# Sensor_Board_0x02_Temperature_Humidity_S.net
KiCad netlist of a schematic drawn in EAGLE
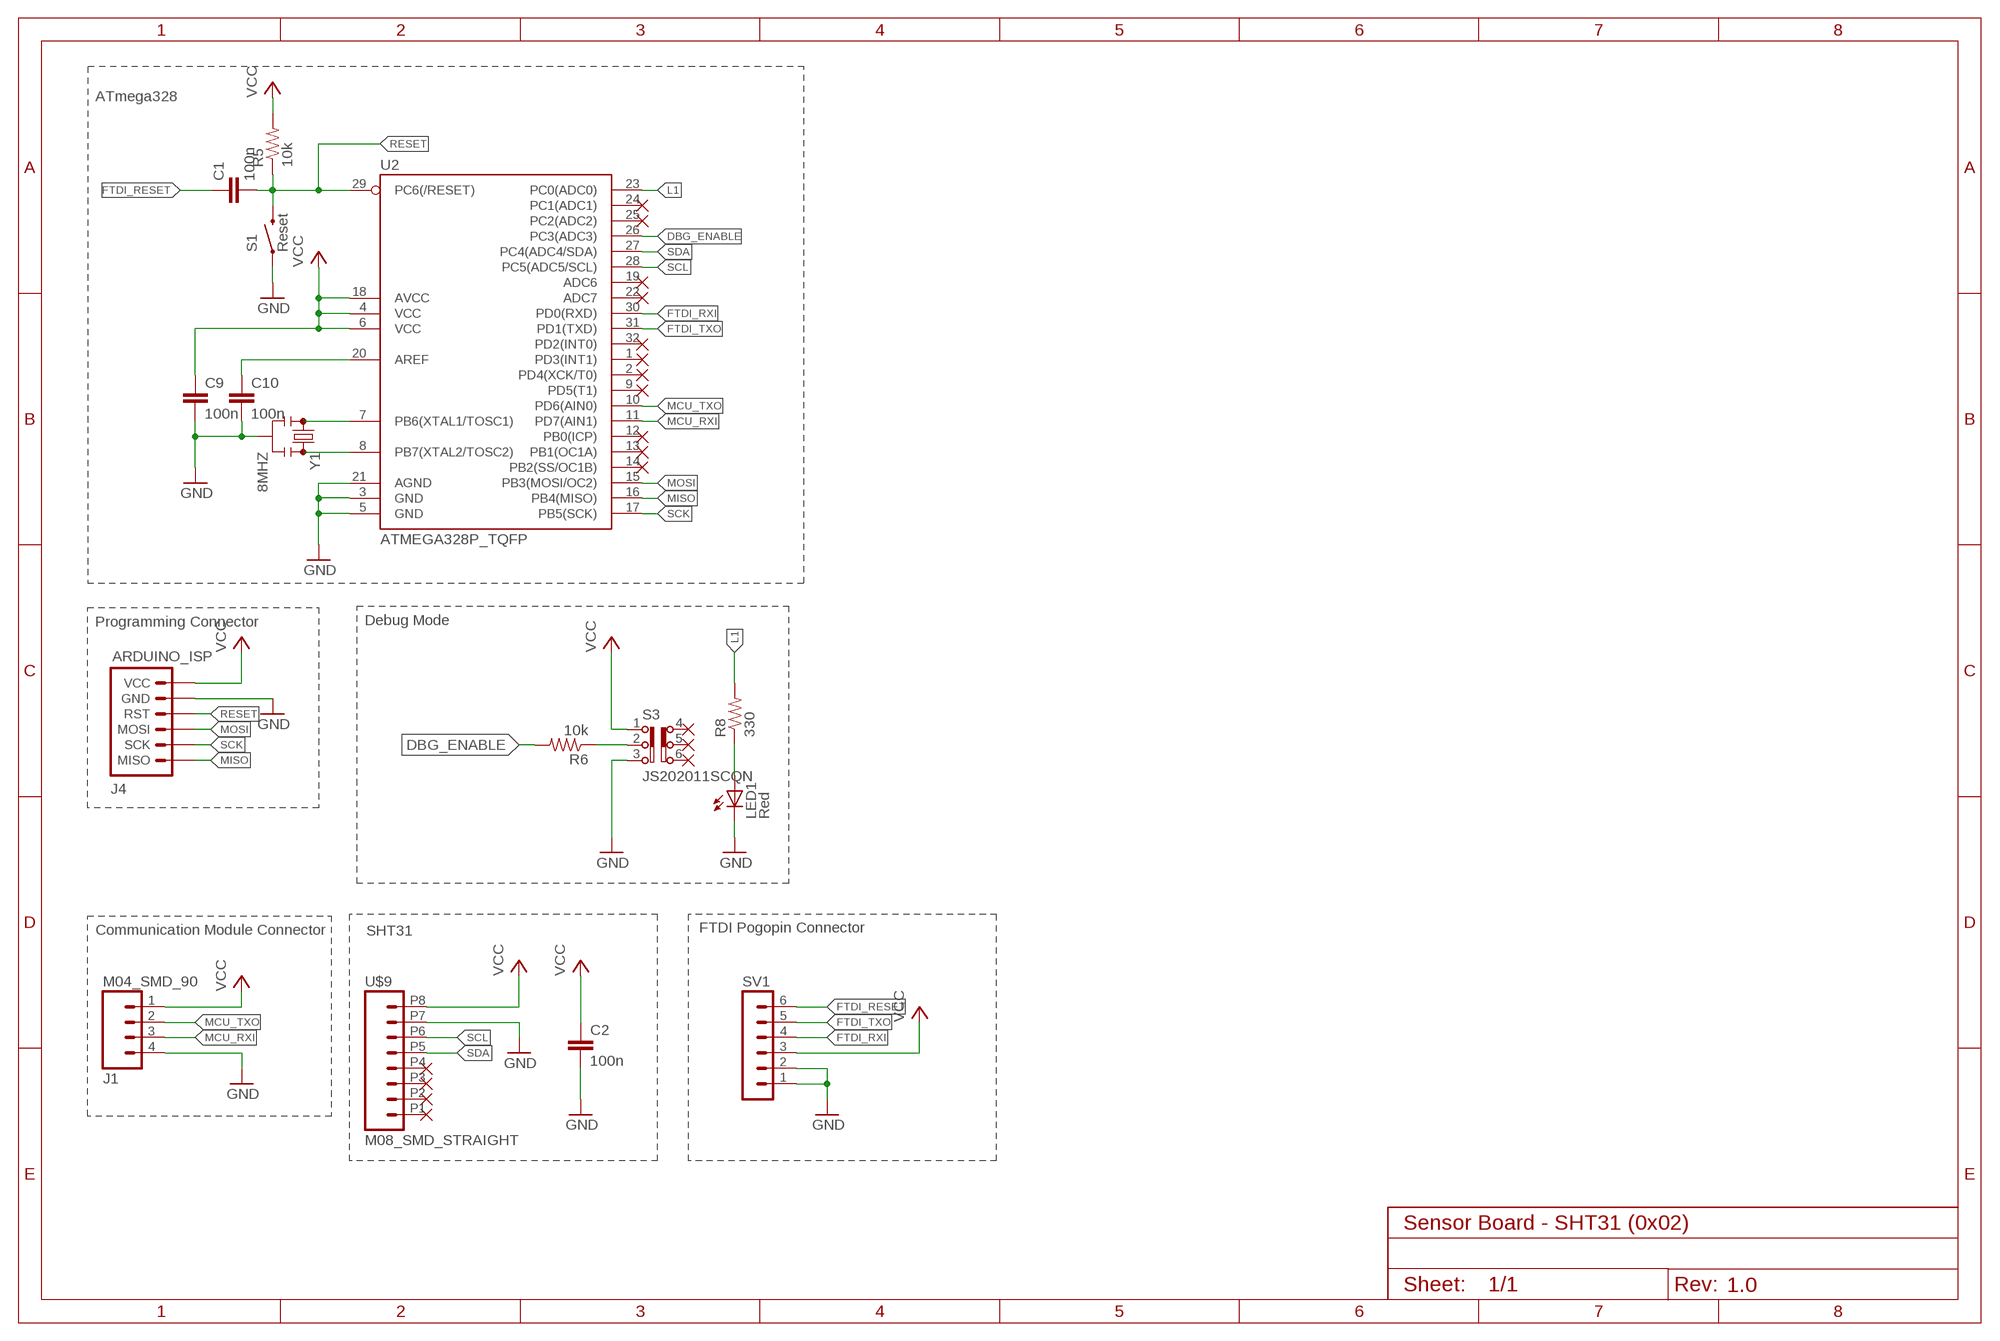
[diagram p0: schematic, sheet 1]

(export (version "E")
  (design (tool "Eeschema 10.0.6"))
  (components
    (comp (ref "C1")
      (value "100n")
      (footprint "eagle-import:C0805")
      (libsource (lib "eagle-import") (part "C"))
    )
    (comp (ref "C2")
      (value "100n")
      (footprint "eagle-import:C0805")
      (libsource (lib "eagle-import") (part "C"))
    )
    (comp (ref "C9")
      (value "100n")
      (footprint "eagle-import:C0805")
      (libsource (lib "eagle-import") (part "C"))
    )
    (comp (ref "C10")
      (value "100n")
      (footprint "eagle-import:C0805")
      (libsource (lib "eagle-import") (part "C"))
    )
    (comp (ref "J1")
      (value "M04_SMD_90")
      (footprint "eagle-import:M04_SMD_90")
      (libsource (lib "eagle-import") (part "M04_SMD_90"))
    )
    (comp (ref "J4")
      (value "ARDUINO_ISP")
      (footprint "eagle-import:M-2X3")
      (libsource (lib "eagle-import") (part "ARDUINO_ISP"))
    )
    (comp (ref "LED1")
      (value "Red")
      (footprint "eagle-import:SML0805")
      (libsource (lib "eagle-import") (part "LEDSML0805"))
    )
    (comp (ref "R5")
      (value "10k")
      (footprint "eagle-import:0805")
      (libsource (lib "eagle-import") (part "RESISTOR0805-RES"))
    )
    (comp (ref "R6")
      (value "10k")
      (footprint "eagle-import:0805")
      (libsource (lib "eagle-import") (part "RESISTOR0805-RES"))
    )
    (comp (ref "R8")
      (value "330")
      (footprint "eagle-import:0805")
      (libsource (lib "eagle-import") (part "RESISTOR0805-RES"))
    )
    (comp (ref "S1")
      (value "Reset")
      (footprint "eagle-import:M-PUSHBUTTON-SMD")
      (libsource (lib "eagle-import") (part "PUSHBUTTON"))
    )
    (comp (ref "S3")
      (value "JS202011SCQN")
      (footprint "eagle-import:JS202011SCQN")
      (libsource (lib "eagle-import") (part "JS202011SCQN"))
    )
    (comp (ref "SV1")
      (value "MA06-1")
      (footprint "eagle-import:MA06-1")
      (libsource (lib "eagle-import") (part "MA06-1"))
    )
    (comp (ref "U$9")
      (value "M08_SMD_STRAIGHT")
      (footprint "eagle-import:M08_SMD_STRAIGHT")
      (libsource (lib "eagle-import") (part "M08_SMD_STRAIGHT"))
    )
    (comp (ref "U2")
      (value "ATMEGA328P_TQFP")
      (footprint "eagle-import:TQFP32-08")
      (libsource (lib "eagle-import") (part "ATMEGA328P_TQFP"))
    )
    (comp (ref "Y1")
      (value "8MHZ")
      (footprint "eagle-import:RESONATOR-SMD")
      (libsource (lib "eagle-import") (part "RESONATOR8MHZ"))
    )
  )
  (nets
    (net (code "1") (name "DBG_ENABLE") (class "Default")
      (node (ref "R6") (pin "2") (pinfunction "2_2") (pintype "passive"))
      (node (ref "U2") (pin "26") (pinfunction "PC3(ADC3)_26") (pintype "bidirectional"))
    )
    (net (code "2") (name "FTDI_RESET") (class "Default")
      (node (ref "C1") (pin "1") (pinfunction "1_1") (pintype "passive"))
      (node (ref "SV1") (pin "6") (pinfunction "6_6") (pintype "passive"))
    )
    (net (code "3") (name "FTDI_RXI") (class "Default")
      (node (ref "SV1") (pin "4") (pinfunction "4_4") (pintype "passive"))
      (node (ref "U2") (pin "30") (pinfunction "PD0(RXD)_30") (pintype "bidirectional"))
    )
    (net (code "4") (name "FTDI_TXO") (class "Default")
      (node (ref "SV1") (pin "5") (pinfunction "5_5") (pintype "passive"))
      (node (ref "U2") (pin "31") (pinfunction "PD1(TXD)_31") (pintype "bidirectional"))
    )
    (net (code "5") (name "GND") (class "Default")
      (node (ref "C10") (pin "2") (pinfunction "2_2") (pintype "passive"))
      (node (ref "C2") (pin "2") (pinfunction "2_2") (pintype "passive"))
      (node (ref "C9") (pin "2") (pinfunction "2_2") (pintype "passive"))
      (node (ref "J1") (pin "4") (pinfunction "4_4") (pintype "passive"))
      (node (ref "J4") (pin "P$5") (pinfunction "GND_P$5") (pintype "passive"))
      (node (ref "LED1") (pin "C") (pinfunction "C_C") (pintype "passive"))
      (node (ref "S1") (pin "1") (pinfunction "LEFT_1") (pintype "passive"))
      (node (ref "S1") (pin "2") (pinfunction "LEFT_2") (pintype "passive"))
      (node (ref "S3") (pin "3") (pinfunction "3_3") (pintype "passive"))
      (node (ref "SV1") (pin "1") (pinfunction "1_1") (pintype "passive"))
      (node (ref "SV1") (pin "2") (pinfunction "2_2") (pintype "passive"))
      (node (ref "U$9") (pin "P7") (pinfunction "7_P7") (pintype "passive"))
      (node (ref "U2") (pin "21") (pinfunction "AGND_21") (pintype "bidirectional"))
      (node (ref "U2") (pin "3") (pinfunction "GND_3") (pintype "bidirectional"))
      (node (ref "U2") (pin "5") (pinfunction "GND_5") (pintype "bidirectional"))
      (node (ref "Y1") (pin "2") (pinfunction "2_2") (pintype "passive"))
    )
    (net (code "6") (name "L1") (class "Default")
      (node (ref "R8") (pin "2") (pinfunction "2_2") (pintype "passive"))
      (node (ref "U2") (pin "23") (pinfunction "PC0(ADC0)_23") (pintype "bidirectional"))
    )
    (net (code "7") (name "MCU_RXI") (class "Default")
      (node (ref "J1") (pin "3") (pinfunction "3_3") (pintype "passive"))
      (node (ref "U2") (pin "11") (pinfunction "PD7(AIN1)_11") (pintype "bidirectional"))
    )
    (net (code "8") (name "MCU_TXO") (class "Default")
      (node (ref "J1") (pin "2") (pinfunction "2_2") (pintype "passive"))
      (node (ref "U2") (pin "10") (pinfunction "PD6(AIN0)_10") (pintype "bidirectional"))
    )
    (net (code "9") (name "MISO") (class "Default")
      (node (ref "J4") (pin "P$1") (pinfunction "MISO_P$1") (pintype "passive"))
      (node (ref "U2") (pin "16") (pinfunction "PB4(MISO)_16") (pintype "bidirectional"))
    )
    (net (code "10") (name "MOSI") (class "Default")
      (node (ref "J4") (pin "P$3") (pinfunction "MOSI_P$3") (pintype "passive"))
      (node (ref "U2") (pin "15") (pinfunction "PB3(MOSI/OC2)_15") (pintype "bidirectional"))
    )
    (net (code "11") (name "Net-(LED1-PadA)") (class "Default")
      (node (ref "LED1") (pin "A") (pinfunction "A_A") (pintype "passive"))
      (node (ref "R8") (pin "1") (pinfunction "1_1") (pintype "passive"))
    )
    (net (code "12") (name "Net-(R6-Pad1)") (class "Default")
      (node (ref "R6") (pin "1") (pinfunction "1_1") (pintype "passive"))
      (node (ref "S3") (pin "2") (pinfunction "2_2") (pintype "passive"))
    )
    (net (code "13") (name "Net-(U2-AREF)") (class "Default")
      (node (ref "C10") (pin "1") (pinfunction "1_1") (pintype "passive"))
      (node (ref "U2") (pin "20") (pinfunction "AREF_20") (pintype "bidirectional"))
    )
    (net (code "14") (name "Net-(U2-PB6(XTAL1{slash}TOSC1))") (class "Default")
      (node (ref "U2") (pin "7") (pinfunction "PB6(XTAL1/TOSC1)_7") (pintype "bidirectional"))
      (node (ref "Y1") (pin "1") (pinfunction "1_1") (pintype "passive"))
    )
    (net (code "15") (name "Net-(U2-PB7(XTAL2{slash}TOSC2))") (class "Default")
      (node (ref "U2") (pin "8") (pinfunction "PB7(XTAL2/TOSC2)_8") (pintype "bidirectional"))
      (node (ref "Y1") (pin "3") (pinfunction "3_3") (pintype "passive"))
    )
    (net (code "16") (name "RESET") (class "Default")
      (node (ref "C1") (pin "2") (pinfunction "2_2") (pintype "passive"))
      (node (ref "J4") (pin "P$4") (pinfunction "RST_P$4") (pintype "passive"))
      (node (ref "R5") (pin "1") (pinfunction "1_1") (pintype "passive"))
      (node (ref "S1") (pin "3") (pinfunction "RIGHT_3") (pintype "passive"))
      (node (ref "S1") (pin "4") (pinfunction "RIGHT_4") (pintype "passive"))
      (node (ref "U2") (pin "29") (pinfunction "PC6(/RESET)_29") (pintype "bidirectional"))
    )
    (net (code "17") (name "SCK") (class "Default")
      (node (ref "J4") (pin "P$2") (pinfunction "SCK_P$2") (pintype "passive"))
      (node (ref "U2") (pin "17") (pinfunction "PB5(SCK)_17") (pintype "bidirectional"))
    )
    (net (code "18") (name "SCL") (class "Default")
      (node (ref "U$9") (pin "P6") (pinfunction "6_P6") (pintype "passive"))
      (node (ref "U2") (pin "28") (pinfunction "PC5(ADC5/SCL)_28") (pintype "bidirectional"))
    )
    (net (code "19") (name "SDA") (class "Default")
      (node (ref "U$9") (pin "P5") (pinfunction "5_P5") (pintype "passive"))
      (node (ref "U2") (pin "27") (pinfunction "PC4(ADC4/SDA)_27") (pintype "bidirectional"))
    )
    (net (code "20") (name "VCC") (class "Default")
      (node (ref "C2") (pin "1") (pinfunction "1_1") (pintype "passive"))
      (node (ref "C9") (pin "1") (pinfunction "1_1") (pintype "passive"))
      (node (ref "J1") (pin "1") (pinfunction "1_1") (pintype "passive"))
      (node (ref "J4") (pin "P$6") (pinfunction "VCC_P$6") (pintype "passive"))
      (node (ref "R5") (pin "2") (pinfunction "2_2") (pintype "passive"))
      (node (ref "S3") (pin "1") (pinfunction "1_1") (pintype "passive"))
      (node (ref "SV1") (pin "3") (pinfunction "3_3") (pintype "passive"))
      (node (ref "U$9") (pin "P8") (pinfunction "8_P8") (pintype "passive"))
      (node (ref "U2") (pin "18") (pinfunction "AVCC_18") (pintype "bidirectional"))
      (node (ref "U2") (pin "4") (pinfunction "VCC_4") (pintype "bidirectional"))
      (node (ref "U2") (pin "6") (pinfunction "VCC_6") (pintype "bidirectional"))
    )
    (net (code "21") (name "unconnected-(S3-Pad4)") (class "Default")
      (node (ref "S3") (pin "4") (pinfunction "4_4") (pintype "passive"))
    )
    (net (code "22") (name "unconnected-(S3-Pad5)") (class "Default")
      (node (ref "S3") (pin "5") (pinfunction "5_5") (pintype "passive"))
    )
    (net (code "23") (name "unconnected-(S3-Pad6)") (class "Default")
      (node (ref "S3") (pin "6") (pinfunction "6_6") (pintype "passive"))
    )
    (net (code "24") (name "unconnected-(U$9-1-PadP1)") (class "Default")
      (node (ref "U$9") (pin "P1") (pinfunction "1_P1") (pintype "passive"))
    )
    (net (code "25") (name "unconnected-(U$9-2-PadP2)") (class "Default")
      (node (ref "U$9") (pin "P2") (pinfunction "2_P2") (pintype "passive"))
    )
    (net (code "26") (name "unconnected-(U$9-3-PadP3)") (class "Default")
      (node (ref "U$9") (pin "P3") (pinfunction "3_P3") (pintype "passive"))
    )
    (net (code "27") (name "unconnected-(U$9-4-PadP4)") (class "Default")
      (node (ref "U$9") (pin "P4") (pinfunction "4_P4") (pintype "passive"))
    )
    (net (code "28") (name "unconnected-(U2-ADC6-Pad19)") (class "Default")
      (node (ref "U2") (pin "19") (pinfunction "ADC6_19") (pintype "bidirectional"))
    )
    (net (code "29") (name "unconnected-(U2-ADC7-Pad22)") (class "Default")
      (node (ref "U2") (pin "22") (pinfunction "ADC7_22") (pintype "bidirectional"))
    )
    (net (code "30") (name "unconnected-(U2-PB0(ICP)-Pad12)") (class "Default")
      (node (ref "U2") (pin "12") (pinfunction "PB0(ICP)_12") (pintype "bidirectional"))
    )
    (net (code "31") (name "unconnected-(U2-PB1(OC1A)-Pad13)") (class "Default")
      (node (ref "U2") (pin "13") (pinfunction "PB1(OC1A)_13") (pintype "bidirectional"))
    )
    (net (code "32") (name "unconnected-(U2-PB2(SS{slash}OC1B)-Pad14)") (class "Default")
      (node (ref "U2") (pin "14") (pinfunction "PB2(SS/OC1B)_14") (pintype "bidirectional"))
    )
    (net (code "33") (name "unconnected-(U2-PC1(ADC1)-Pad24)") (class "Default")
      (node (ref "U2") (pin "24") (pinfunction "PC1(ADC1)_24") (pintype "bidirectional"))
    )
    (net (code "34") (name "unconnected-(U2-PC2(ADC2)-Pad25)") (class "Default")
      (node (ref "U2") (pin "25") (pinfunction "PC2(ADC2)_25") (pintype "bidirectional"))
    )
    (net (code "35") (name "unconnected-(U2-PD2(INT0)-Pad32)") (class "Default")
      (node (ref "U2") (pin "32") (pinfunction "PD2(INT0)_32") (pintype "bidirectional"))
    )
    (net (code "36") (name "unconnected-(U2-PD3(INT1)-Pad1)") (class "Default")
      (node (ref "U2") (pin "1") (pinfunction "PD3(INT1)_1") (pintype "bidirectional"))
    )
    (net (code "37") (name "unconnected-(U2-PD4(XCK{slash}T0)-Pad2)") (class "Default")
      (node (ref "U2") (pin "2") (pinfunction "PD4(XCK/T0)_2") (pintype "bidirectional"))
    )
    (net (code "38") (name "unconnected-(U2-PD5(T1)-Pad9)") (class "Default")
      (node (ref "U2") (pin "9") (pinfunction "PD5(T1)_9") (pintype "bidirectional"))
    )
  )
)
